# MCU_main.net
KiCad netlist of a schematic drawn in Altium Designer
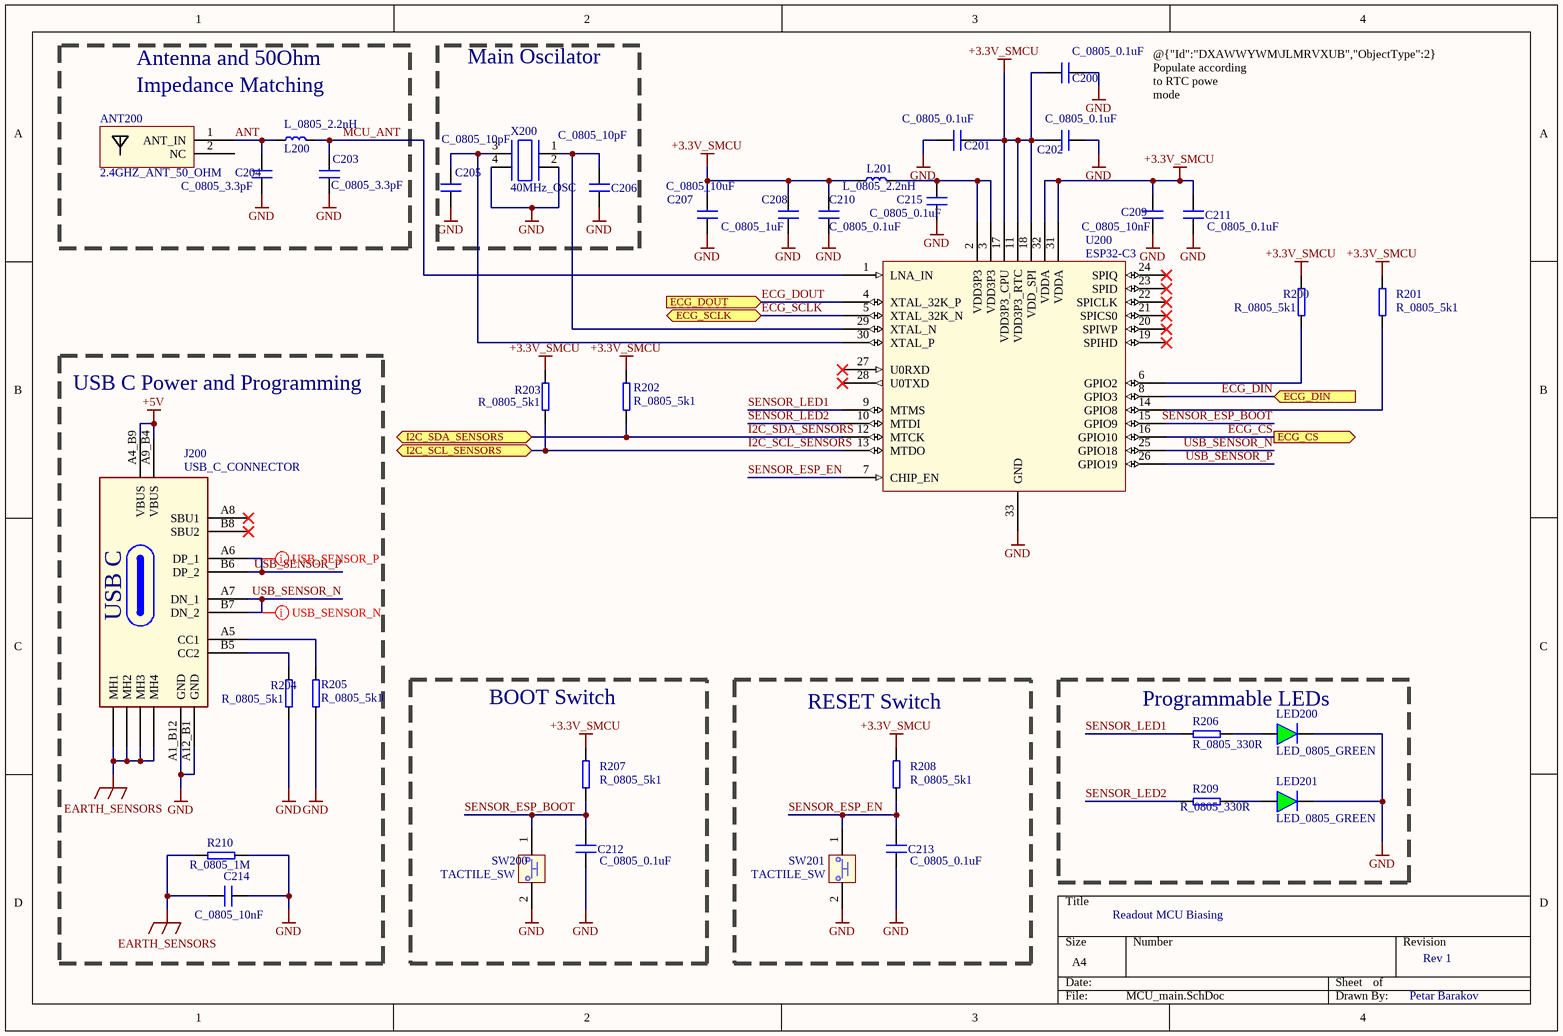
[diagram p0: MCU_main.SchDoc]

(export (version "E")
  (design (tool "Eeschema 10.0.6"))
  (components
    (comp (ref "ANT200")
      (value "2.4GHZ_ANT_50_OHM")
      (footprint "Chip2PinSM127P600-8N")
      (description "2.4GHz Chip Antenna 50 Ohm Impedance ANT2012LL00R2400A")
      (libsource (lib "Petar B") (part "2.4GHZ_ANT_50_OHM"))
    )
    (comp (ref "C200")
      (value "C_0805_0.1uF")
      (footprint "CAP_0805")
      (fields (field (name "JLC PART NUMBER") "C28233"))
      (libsource (lib "Petar B") (part "0.1uF 0805"))
    )
    (comp (ref "C201")
      (value "C_0805_0.1uF")
      (footprint "CAP_0805")
      (fields (field (name "JLC PART NUMBER") "C28233"))
      (libsource (lib "Petar B") (part "0.1uF 0805"))
    )
    (comp (ref "C202")
      (value "C_0805_0.1uF")
      (footprint "CAP_0805")
      (fields (field (name "JLC PART NUMBER") "C28233"))
      (libsource (lib "Petar B") (part "0.1uF 0805"))
    )
    (comp (ref "C203")
      (value "C_0805_3.3pF")
      (footprint "CAP_0805")
      (description "3.3pF Capaciror")
      (fields (field (name "JLC PART NUMBER") "C1811"))
      (libsource (lib "Petar B") (part "3.3pF 0805"))
    )
    (comp (ref "C204")
      (value "C_0805_3.3pF")
      (footprint "CAP_0805")
      (description "3.3pF Capaciror")
      (fields (field (name "JLC PART NUMBER") "C1811"))
      (libsource (lib "Petar B") (part "3.3pF 0805"))
    )
    (comp (ref "C205")
      (value "C_0805_10pF")
      (footprint "CAP_0805")
      (fields (field (name "JLC PART NUMBER") "C107107"))
      (libsource (lib "Petar B") (part "0.1uF 0805"))
    )
    (comp (ref "C206")
      (value "C_0805_10pF")
      (footprint "CAP_0805")
      (fields (field (name "JLC PART NUMBER") "C107107"))
      (libsource (lib "Petar B") (part "0.1uF 0805"))
    )
    (comp (ref "C207")
      (value "C_0805_10uF")
      (footprint "CAP_0805")
      (fields (field (name "JLC PART NUMBER") "C15850"))
      (libsource (lib "Petar B") (part "10uF 0805"))
    )
    (comp (ref "C208")
      (value "C_0805_1uF")
      (footprint "CAP_0805")
      (fields (field (name "JLC PART NUMBER") "C28323"))
      (libsource (lib "Petar B") (part "1uF 0805"))
    )
    (comp (ref "C209")
      (value "C_0805_10nF")
      (footprint "CAP_0805")
      (fields (field (name "JLC PART NUMBER") "C1710"))
      (libsource (lib "Petar B") (part "0.1uF 0805"))
    )
    (comp (ref "C210")
      (value "C_0805_0.1uF")
      (footprint "CAP_0805")
      (fields (field (name "JLC PART NUMBER") "C28233"))
      (libsource (lib "Petar B") (part "0.1uF 0805"))
    )
    (comp (ref "C211")
      (value "C_0805_0.1uF")
      (footprint "CAP_0805")
      (fields (field (name "JLC PART NUMBER") "C28233"))
      (libsource (lib "Petar B") (part "0.1uF 0805"))
    )
    (comp (ref "C212")
      (value "C_0805_0.1uF")
      (footprint "CAP_0805")
      (fields (field (name "JLC PART NUMBER") "C28233"))
      (libsource (lib "Petar B") (part "0.1uF 0805"))
    )
    (comp (ref "C213")
      (value "C_0805_0.1uF")
      (footprint "CAP_0805")
      (fields (field (name "JLC PART NUMBER") "C28233"))
      (libsource (lib "Petar B") (part "0.1uF 0805"))
    )
    (comp (ref "C214")
      (value "C_0805_10nF")
      (footprint "CAP_0805")
      (fields (field (name "JLC PART NUMBER") "C1710"))
      (libsource (lib "Petar B") (part "0.1uF 0805"))
    )
    (comp (ref "C215")
      (value "C_0805_0.1uF")
      (footprint "CAP_0805")
      (fields (field (name "JLC PART NUMBER") "C28233"))
      (libsource (lib "Petar B") (part "0.1uF 0805"))
    )
    (comp (ref "J200")
      (value "USB_C_CONNECTOR")
      (footprint "USB_C_CONNECTOR-Footprint-1")
      (description "USB2.0, Type C, Top Mount, Ch 1.68MM, Dual Row SMT / Tap/rl")
      (fields (field (name "JLC PART NUMBER") "C2831450"))
      (libsource (lib "Petar B") (part "conn_usb_c"))
    )
    (comp (ref "L200")
      (value "L_0805_2.2nH")
      (footprint "L_0805")
      (description "Required a minimum current of 500mA and a resonant frequrency of at least 6GHz")
      (fields (field (name "JLC PART NUMBER") "C964055"))
      (libsource (lib "Petar B") (part "0805 2.2uH"))
    )
    (comp (ref "L201")
      (value "L_0805_2.2nH")
      (footprint "L_0805")
      (description "Required a minimum current of 500mA and a resonant frequrency of at least 6GHz")
      (fields (field (name "JLC PART NUMBER") "C964055"))
      (libsource (lib "Petar B") (part "0805 2.2uH"))
    )
    (comp (ref "LED200")
      (value "LED_0805_GREEN")
      (footprint "LED_0806")
      (description "LED, Green, SMD, 0805 [2012 Metric], 30 mA, 2 V, 570 nm")
      (fields (field (name "JLC PART NUMBER") "C2297"))
      (libsource (lib "Petar B") (part "LED_GREEN"))
    )
    (comp (ref "LED201")
      (value "LED_0805_GREEN")
      (footprint "LED_0806")
      (description "LED, Green, SMD, 0805 [2012 Metric], 30 mA, 2 V, 570 nm")
      (fields (field (name "JLC PART NUMBER") "C2297"))
      (libsource (lib "Petar B") (part "LED_GREEN"))
    )
    (comp (ref "R200")
      (value "R_0805_5k1")
      (footprint "0805_RES")
      (fields (field (name "JLC PART NUMBER") "C27834"))
      (libsource (lib "Petar B") (part "4.7k0805"))
    )
    (comp (ref "R201")
      (value "R_0805_5k1")
      (footprint "0805_RES")
      (fields (field (name "JLC PART NUMBER") "C27834"))
      (libsource (lib "Petar B") (part "4.7k0805"))
    )
    (comp (ref "R202")
      (value "R_0805_5k1")
      (footprint "0805_RES")
      (fields (field (name "JLC PART NUMBER") "C27834"))
      (libsource (lib "Petar B") (part "4.7k0805"))
    )
    (comp (ref "R203")
      (value "R_0805_5k1")
      (footprint "0805_RES")
      (fields (field (name "JLC PART NUMBER") "C27834"))
      (libsource (lib "Petar B") (part "4.7k0805"))
    )
    (comp (ref "R204")
      (value "R_0805_5k1")
      (footprint "0805_RES")
      (fields (field (name "JLC PART NUMBER") "C27834"))
      (libsource (lib "Petar B") (part "4.7k0805"))
    )
    (comp (ref "R205")
      (value "R_0805_5k1")
      (footprint "0805_RES")
      (fields (field (name "JLC PART NUMBER") "C27834"))
      (libsource (lib "Petar B") (part "4.7k0805"))
    )
    (comp (ref "R206")
      (value "R_0805_330R")
      (footprint "0805_RES")
      (fields (field (name "JLC PART NUMBER") "C17630"))
      (libsource (lib "Petar B") (part "4.7k0805"))
    )
    (comp (ref "R207")
      (value "R_0805_5k1")
      (footprint "0805_RES")
      (fields (field (name "JLC PART NUMBER") "C27834"))
      (libsource (lib "Petar B") (part "4.7k0805"))
    )
    (comp (ref "R208")
      (value "R_0805_5k1")
      (footprint "0805_RES")
      (fields (field (name "JLC PART NUMBER") "C27834"))
      (libsource (lib "Petar B") (part "4.7k0805"))
    )
    (comp (ref "R209")
      (value "R_0805_330R")
      (footprint "0805_RES")
      (fields (field (name "JLC PART NUMBER") "C17630"))
      (libsource (lib "Petar B") (part "4.7k0805"))
    )
    (comp (ref "R210")
      (value "R_0805_1M")
      (footprint "0805_RES")
      (fields (field (name "JLC PART NUMBER") "C131391"))
      (libsource (lib "Petar B") (part "R_symbol"))
    )
    (comp (ref "SW200")
      (value "TACTILE_SW")
      (footprint "TACTILE_SW-Footprint-1")
      (fields (field (name "JLC PART NUMBER") "C455280"))
      (libsource (lib "Petar B") (part "TACTILE_SW"))
    )
    (comp (ref "SW201")
      (value "TACTILE_SW")
      (footprint "TACTILE_SW-Footprint-1")
      (fields (field (name "JLC PART NUMBER") "C455280"))
      (libsource (lib "Petar B") (part "TACTILE_SW"))
    )
    (comp (ref "U200")
      (value "ESP32-C3")
      (footprint "QFN127P600-8N")
      (description "33 pin ESP32_C3 Microcontroller")
      (fields (field (name "JLC PART NUMBER") "C2858491"))
      (libsource (lib "Petar B") (part "ESP32-C3_symbol"))
    )
    (comp (ref "X200")
      (value "40MHz_OSC")
      (footprint "40MHz_OSC-Footprint-1")
      (description "40 MHZ Oscillator, 10pF load capacitance")
      (fields (field (name "JLC PART NUMBER") "C426988"))
      (libsource (lib "Petar B") (part "OSC_SYMB"))
    )
  )
  (nets
    (net (code "1") (name "+3.3V_SMCU") (class "Default")
      (node (ref "C200") (pin "1") (pinfunction "1_1") (pintype "passive"))
      (node (ref "C201") (pin "2") (pinfunction "2_2") (pintype "passive"))
      (node (ref "C202") (pin "1") (pinfunction "1_1") (pintype "passive"))
      (node (ref "C207") (pin "2") (pinfunction "2_2") (pintype "passive"))
      (node (ref "C208") (pin "2") (pinfunction "2_2") (pintype "passive"))
      (node (ref "C209") (pin "2") (pinfunction "2_2") (pintype "passive"))
      (node (ref "C210") (pin "1") (pinfunction "1_1") (pintype "passive"))
      (node (ref "C211") (pin "2") (pinfunction "2_2") (pintype "passive"))
      (node (ref "L201") (pin "1") (pinfunction "1_1") (pintype "passive"))
      (node (ref "R200") (pin "1") (pinfunction "1_1") (pintype "passive"))
      (node (ref "R201") (pin "1") (pinfunction "1_1") (pintype "passive"))
      (node (ref "R202") (pin "1") (pinfunction "1_1") (pintype "passive"))
      (node (ref "R203") (pin "1") (pinfunction "1_1") (pintype "passive"))
      (node (ref "R207") (pin "1") (pinfunction "1_1") (pintype "passive"))
      (node (ref "R208") (pin "1") (pinfunction "1_1") (pintype "passive"))
      (node (ref "U200") (pin "11") (pinfunction "VDD3P3_RTC_11") (pintype "power_in"))
      (node (ref "U200") (pin "17") (pinfunction "VDD3P3_CPU_17") (pintype "power_in"))
      (node (ref "U200") (pin "18") (pinfunction "VDD_SPI_18") (pintype "power_in"))
      (node (ref "U200") (pin "31") (pinfunction "VDDA_31") (pintype "power_in"))
      (node (ref "U200") (pin "32") (pinfunction "VDDA_32") (pintype "power_in"))
    )
    (net (code "2") (name "+5V") (class "Default")
      (node (ref "J200") (pin "A4_B9") (pinfunction "VBUS_A4_B9") (pintype "passive"))
      (node (ref "J200") (pin "A9_B4") (pinfunction "VBUS_A9_B4") (pintype "passive"))
    )
    (net (code "3") (name "/ANT") (class "Default")
      (node (ref "ANT200") (pin "1") (pinfunction "ANT_IN_1") (pintype "passive"))
      (node (ref "C204") (pin "2") (pinfunction "2_2") (pintype "passive"))
      (node (ref "L200") (pin "1") (pinfunction "1_1") (pintype "passive"))
    )
    (net (code "4") (name "/ECG_CS") (class "Default")
      (node (ref "U200") (pin "16") (pinfunction "GPIO10_16") (pintype "bidirectional"))
    )
    (net (code "5") (name "/ECG_DIN") (class "Default")
      (node (ref "U200") (pin "8") (pinfunction "GPIO3_8") (pintype "bidirectional"))
    )
    (net (code "6") (name "/ECG_DOUT") (class "Default")
      (node (ref "U200") (pin "4") (pinfunction "XTAL_32K_P_4") (pintype "bidirectional"))
    )
    (net (code "7") (name "/ECG_SCLK") (class "Default")
      (node (ref "U200") (pin "5") (pinfunction "XTAL_32K_N_5") (pintype "bidirectional"))
    )
    (net (code "8") (name "/I2C_SCL_SENSORS") (class "Default")
      (node (ref "R203") (pin "2") (pinfunction "2_2") (pintype "passive"))
      (node (ref "U200") (pin "13") (pinfunction "MTDO_13") (pintype "bidirectional"))
    )
    (net (code "9") (name "/I2C_SDA_SENSORS") (class "Default")
      (node (ref "R202") (pin "2") (pinfunction "2_2") (pintype "passive"))
      (node (ref "U200") (pin "12") (pinfunction "MTCK_12") (pintype "bidirectional"))
    )
    (net (code "10") (name "/MCU_ANT") (class "Default")
      (node (ref "C203") (pin "2") (pinfunction "2_2") (pintype "passive"))
      (node (ref "L200") (pin "2") (pinfunction "2_2") (pintype "passive"))
      (node (ref "U200") (pin "1") (pinfunction "LNA_IN_1") (pintype "input"))
    )
    (net (code "11") (name "/SENSOR_ESP_BOOT") (class "Default")
      (node (ref "C212") (pin "2") (pinfunction "2_2") (pintype "passive"))
      (node (ref "R207") (pin "2") (pinfunction "2_2") (pintype "passive"))
      (node (ref "SW200") (pin "1") (pinfunction "1_1") (pintype "passive"))
      (node (ref "U200") (pin "15") (pinfunction "GPIO9_15") (pintype "bidirectional"))
    )
    (net (code "12") (name "/SENSOR_ESP_EN") (class "Default")
      (node (ref "C213") (pin "2") (pinfunction "2_2") (pintype "passive"))
      (node (ref "R208") (pin "2") (pinfunction "2_2") (pintype "passive"))
      (node (ref "SW201") (pin "1") (pinfunction "1_1") (pintype "passive"))
      (node (ref "U200") (pin "7") (pinfunction "CHIP_EN_7") (pintype "input"))
    )
    (net (code "13") (name "/SENSOR_LED1") (class "Default")
      (node (ref "R206") (pin "2") (pinfunction "2_2") (pintype "passive"))
      (node (ref "U200") (pin "9") (pinfunction "MTMS_9") (pintype "bidirectional"))
    )
    (net (code "14") (name "/SENSOR_LED2") (class "Default")
      (node (ref "R209") (pin "2") (pinfunction "2_2") (pintype "passive"))
      (node (ref "U200") (pin "10") (pinfunction "MTDI_10") (pintype "bidirectional"))
    )
    (net (code "15") (name "/USB_SENSOR_N") (class "Default")
      (node (ref "J200") (pin "A7") (pinfunction "DN_1_A7") (pintype "passive"))
      (node (ref "J200") (pin "B7") (pinfunction "DN_2_B7") (pintype "passive"))
      (node (ref "U200") (pin "25") (pinfunction "GPIO18_25") (pintype "bidirectional"))
    )
    (net (code "16") (name "/USB_SENSOR_P") (class "Default")
      (node (ref "J200") (pin "A6") (pinfunction "DP_1_A6") (pintype "passive"))
      (node (ref "J200") (pin "B6") (pinfunction "DP_2_B6") (pintype "passive"))
      (node (ref "U200") (pin "26") (pinfunction "GPIO19_26") (pintype "bidirectional"))
    )
    (net (code "17") (name "EARTH_SENSORS") (class "Default")
      (node (ref "C214") (pin "1") (pinfunction "1_1") (pintype "passive"))
      (node (ref "J200") (pin "MH1") (pinfunction "MH1_MH1") (pintype "passive"))
      (node (ref "J200") (pin "MH2") (pinfunction "MH2_MH2") (pintype "passive"))
      (node (ref "J200") (pin "MH3") (pinfunction "MH3_MH3") (pintype "passive"))
      (node (ref "J200") (pin "MH4") (pinfunction "MH4_MH4") (pintype "passive"))
      (node (ref "R210") (pin "2") (pinfunction "2_2") (pintype "passive"))
    )
    (net (code "18") (name "GND") (class "Default")
      (node (ref "C200") (pin "2") (pinfunction "2_2") (pintype "passive"))
      (node (ref "C201") (pin "1") (pinfunction "1_1") (pintype "passive"))
      (node (ref "C202") (pin "2") (pinfunction "2_2") (pintype "passive"))
      (node (ref "C203") (pin "1") (pinfunction "1_1") (pintype "passive"))
      (node (ref "C204") (pin "1") (pinfunction "1_1") (pintype "passive"))
      (node (ref "C205") (pin "1") (pinfunction "1_1") (pintype "passive"))
      (node (ref "C206") (pin "1") (pinfunction "1_1") (pintype "passive"))
      (node (ref "C207") (pin "1") (pinfunction "1_1") (pintype "passive"))
      (node (ref "C208") (pin "1") (pinfunction "1_1") (pintype "passive"))
      (node (ref "C209") (pin "1") (pinfunction "1_1") (pintype "passive"))
      (node (ref "C210") (pin "2") (pinfunction "2_2") (pintype "passive"))
      (node (ref "C211") (pin "1") (pinfunction "1_1") (pintype "passive"))
      (node (ref "C212") (pin "1") (pinfunction "1_1") (pintype "passive"))
      (node (ref "C213") (pin "1") (pinfunction "1_1") (pintype "passive"))
      (node (ref "C214") (pin "2") (pinfunction "2_2") (pintype "passive"))
      (node (ref "C215") (pin "2") (pinfunction "2_2") (pintype "passive"))
      (node (ref "J200") (pin "A12_B1") (pinfunction "GND_A12_B1") (pintype "passive"))
      (node (ref "J200") (pin "A1_B12") (pinfunction "GND_A1_B12") (pintype "passive"))
      (node (ref "LED200") (pin "1") (pinfunction "1_1") (pintype "passive"))
      (node (ref "LED201") (pin "1") (pinfunction "1_1") (pintype "passive"))
      (node (ref "R204") (pin "2") (pinfunction "2_2") (pintype "passive"))
      (node (ref "R205") (pin "2") (pinfunction "2_2") (pintype "passive"))
      (node (ref "R210") (pin "1") (pinfunction "1_1") (pintype "passive"))
      (node (ref "SW200") (pin "2") (pinfunction "2_2") (pintype "passive"))
      (node (ref "SW201") (pin "2") (pinfunction "2_2") (pintype "passive"))
      (node (ref "U200") (pin "33") (pinfunction "GND_33") (pintype "power_in"))
      (node (ref "X200") (pin "2") (pinfunction "2_2") (pintype "passive"))
      (node (ref "X200") (pin "4") (pinfunction "4_4") (pintype "passive"))
    )
    (net (code "19") (name "Net-(C215-Pad1)") (class "Default")
      (node (ref "C215") (pin "1") (pinfunction "1_1") (pintype "passive"))
      (node (ref "L201") (pin "2") (pinfunction "2_2") (pintype "passive"))
      (node (ref "U200") (pin "2") (pinfunction "VDD3P3_2") (pintype "power_in"))
      (node (ref "U200") (pin "3") (pinfunction "VDD3P3_3") (pintype "power_in"))
    )
    (net (code "20") (name "Net-(J200-CC1)") (class "Default")
      (node (ref "J200") (pin "A5") (pinfunction "CC1_A5") (pintype "passive"))
      (node (ref "R205") (pin "1") (pinfunction "1_1") (pintype "passive"))
    )
    (net (code "21") (name "Net-(J200-CC2)") (class "Default")
      (node (ref "J200") (pin "B5") (pinfunction "CC2_B5") (pintype "passive"))
      (node (ref "R204") (pin "1") (pinfunction "1_1") (pintype "passive"))
    )
    (net (code "22") (name "Net-(LED200-Pad2)") (class "Default")
      (node (ref "LED200") (pin "2") (pinfunction "2_2") (pintype "passive"))
      (node (ref "R206") (pin "1") (pinfunction "1_1") (pintype "passive"))
    )
    (net (code "23") (name "Net-(LED201-Pad2)") (class "Default")
      (node (ref "LED201") (pin "2") (pinfunction "2_2") (pintype "passive"))
      (node (ref "R209") (pin "1") (pinfunction "1_1") (pintype "passive"))
    )
    (net (code "24") (name "Net-(U200-GPIO2)") (class "Default")
      (node (ref "R200") (pin "2") (pinfunction "2_2") (pintype "passive"))
      (node (ref "U200") (pin "6") (pinfunction "GPIO2_6") (pintype "bidirectional"))
    )
    (net (code "25") (name "Net-(U200-GPIO8)") (class "Default")
      (node (ref "R201") (pin "2") (pinfunction "2_2") (pintype "passive"))
      (node (ref "U200") (pin "14") (pinfunction "GPIO8_14") (pintype "bidirectional"))
    )
    (net (code "26") (name "Net-(U200-XTAL_N)") (class "Default")
      (node (ref "C206") (pin "2") (pinfunction "2_2") (pintype "passive"))
      (node (ref "U200") (pin "29") (pinfunction "XTAL_N_29") (pintype "bidirectional"))
      (node (ref "X200") (pin "1") (pinfunction "1_1") (pintype "passive"))
    )
    (net (code "27") (name "Net-(U200-XTAL_P)") (class "Default")
      (node (ref "C205") (pin "2") (pinfunction "2_2") (pintype "passive"))
      (node (ref "U200") (pin "30") (pinfunction "XTAL_P_30") (pintype "bidirectional"))
      (node (ref "X200") (pin "3") (pinfunction "3_3") (pintype "passive"))
    )
    (net (code "28") (name "unconnected-(ANT200-NC-Pad2)") (class "Default")
      (node (ref "ANT200") (pin "2") (pinfunction "NC_2") (pintype "passive"))
    )
    (net (code "29") (name "unconnected-(J200-SBU1-PadA8)") (class "Default")
      (node (ref "J200") (pin "A8") (pinfunction "SBU1_A8") (pintype "passive+no_connect"))
    )
    (net (code "30") (name "unconnected-(J200-SBU2-PadB8)") (class "Default")
      (node (ref "J200") (pin "B8") (pinfunction "SBU2_B8") (pintype "passive+no_connect"))
    )
    (net (code "31") (name "unconnected-(U200-SPICLK-Pad22)") (class "Default")
      (node (ref "U200") (pin "22") (pinfunction "SPICLK_22") (pintype "bidirectional+no_connect"))
    )
    (net (code "32") (name "unconnected-(U200-SPICS0-Pad21)") (class "Default")
      (node (ref "U200") (pin "21") (pinfunction "SPICS0_21") (pintype "bidirectional+no_connect"))
    )
    (net (code "33") (name "unconnected-(U200-SPID-Pad23)") (class "Default")
      (node (ref "U200") (pin "23") (pinfunction "SPID_23") (pintype "bidirectional+no_connect"))
    )
    (net (code "34") (name "unconnected-(U200-SPIHD-Pad19)") (class "Default")
      (node (ref "U200") (pin "19") (pinfunction "SPIHD_19") (pintype "bidirectional+no_connect"))
    )
    (net (code "35") (name "unconnected-(U200-SPIQ-Pad24)") (class "Default")
      (node (ref "U200") (pin "24") (pinfunction "SPIQ_24") (pintype "bidirectional+no_connect"))
    )
    (net (code "36") (name "unconnected-(U200-SPIWP-Pad20)") (class "Default")
      (node (ref "U200") (pin "20") (pinfunction "SPIWP_20") (pintype "bidirectional+no_connect"))
    )
    (net (code "37") (name "unconnected-(U200-U0RXD-Pad27)") (class "Default")
      (node (ref "U200") (pin "27") (pinfunction "U0RXD_27") (pintype "input+no_connect"))
    )
    (net (code "38") (name "unconnected-(U200-U0TXD-Pad28)") (class "Default")
      (node (ref "U200") (pin "28") (pinfunction "U0TXD_28") (pintype "output+no_connect"))
    )
  )
)
